# dc-dc.net
KiCad netlist of a schematic drawn in Altium Designer
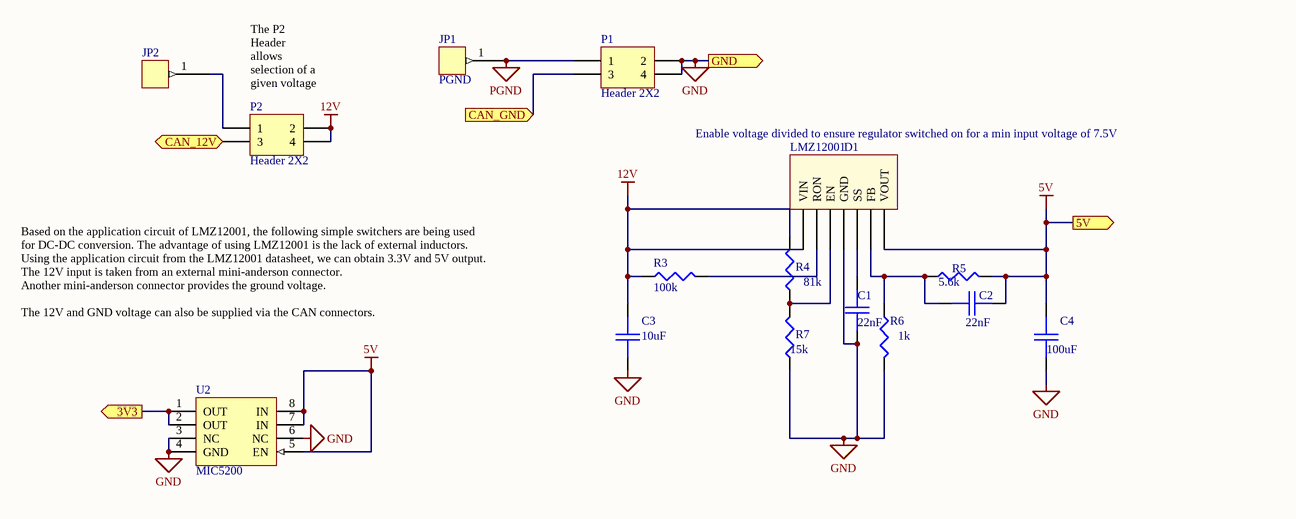
[diagram p0: dc-dc.SchDoc]

(export (version "E")
  (design (tool "Eeschema 10.0.6"))
  (components
    (comp (ref "C1")
      (value "22nF")
      (footprint "0603")
      (description "Capacitor")
      (fields (field (name "Comment") "CAP"))
      (libsource (lib "RCLDQ") (part "CAP"))
    )
    (comp (ref "C2")
      (value "22nF")
      (footprint "0603")
      (description "Capacitor")
      (fields (field (name "Comment") "CAP"))
      (libsource (lib "RCLDQ") (part "CAP"))
    )
    (comp (ref "C3")
      (value "10uF")
      (footprint "1206")
      (description "Capacitor")
      (fields (field (name "Comment") "CAP"))
      (libsource (lib "RCLDQ") (part "CAP"))
    )
    (comp (ref "C4")
      (value "100uF")
      (footprint "1206")
      (description "Capacitor")
      (fields (field (name "Comment") "CAP"))
      (libsource (lib "RCLDQ") (part "CAP"))
    )
    (comp (ref "D1")
      (value "DC-DC SWITCHER")
      (footprint "PFM-7")
      (libsource (lib "add-schematic-library") (part "lmz12001"))
    )
    (comp (ref "JP1")
      (value "PGND")
      (footprint "POWERPOLE25A")
      (description "Power Ground (currently assumed that it is provided through a min-anderson connector)")
      (libsource (lib "Connectors") (part "CON1"))
    )
    (comp (ref "JP2")
      (value "CON1")
      (footprint "POWERPOLE25A")
      (description "Currently assumed that the mini-anderson connector provides 12V")
      (libsource (lib "Connectors") (part "CON1"))
    )
    (comp (ref "P1")
      (value "Header 2X2")
      (footprint "HDR2X2")
      (description "Header, 2-Pin, Dual row")
      (fields (field (name "PUBLISHER") "Altium Limited"))
      (libsource (lib "Miscellaneous Connectors") (part "Header 2X2"))
    )
    (comp (ref "P2")
      (value "Header 2X2")
      (footprint "HDR2X2")
      (description "Header, 2-Pin, Dual row")
      (fields (field (name "PUBLISHER") "Altium Limited"))
      (libsource (lib "Miscellaneous Connectors") (part "Header 2X2"))
    )
    (comp (ref "R3")
      (value "100k")
      (footprint "0603")
      (description "Resistor")
      (fields (field (name "Comment") "RES1"))
      (libsource (lib "RCLDQ") (part "RES1"))
    )
    (comp (ref "R4")
      (value "81k")
      (footprint "0603")
      (description "Resistor")
      (fields (field (name "Comment") "RES1"))
      (libsource (lib "RCLDQ") (part "RES1"))
    )
    (comp (ref "R5")
      (value "5.6k")
      (footprint "0603")
      (description "Resistor")
      (fields (field (name "Comment") "RES1"))
      (libsource (lib "RCLDQ") (part "RES1"))
    )
    (comp (ref "R6")
      (value "1k")
      (footprint "0603")
      (description "Resistor")
      (fields (field (name "Comment") "RES1"))
      (libsource (lib "RCLDQ") (part "RES1"))
    )
    (comp (ref "R7")
      (value "15k")
      (footprint "0603")
      (description "Resistor")
      (fields (field (name "Comment") "RES1"))
      (libsource (lib "RCLDQ") (part "RES1"))
    )
    (comp (ref "U2")
      (value "MIC5200")
      (footprint "SO8")
      (description "MIC5200 - SO8")
      (libsource (lib "Regulators") (part "MIC5200"))
    )
  )
  (nets
    (net (code "1") (name "/3V3") (class "Default")
      (node (ref "U2") (pin "1") (pinfunction "OUT_1") (pintype "power_in"))
      (node (ref "U2") (pin "2") (pinfunction "OUT_2") (pintype "power_in"))
    )
    (net (code "2") (name "/CAN_12V") (class "Default")
      (node (ref "P2") (pin "3") (pinfunction "3_3") (pintype "passive"))
    )
    (net (code "3") (name "/CAN_GND") (class "Default")
      (node (ref "P1") (pin "3") (pinfunction "3_3") (pintype "passive"))
    )
    (net (code "4") (name "5V") (class "Default")
      (node (ref "C2") (pin "2") (pinfunction "2_2") (pintype "passive"))
      (node (ref "C4") (pin "1") (pinfunction "1_1") (pintype "passive"))
      (node (ref "D1") (pin "7") (pinfunction "VOUT_7") (pintype "passive"))
      (node (ref "R5") (pin "2") (pinfunction "2_2") (pintype "passive"))
      (node (ref "U2") (pin "5") (pinfunction "EN_5") (pintype "input"))
      (node (ref "U2") (pin "7") (pinfunction "IN_7") (pintype "power_in"))
      (node (ref "U2") (pin "8") (pinfunction "IN_8") (pintype "power_in"))
    )
    (net (code "5") (name "12V") (class "Default")
      (node (ref "C3") (pin "1") (pinfunction "1_1") (pintype "passive"))
      (node (ref "D1") (pin "1") (pinfunction "VIN_1") (pintype "passive"))
      (node (ref "P2") (pin "2") (pinfunction "2_2") (pintype "passive"))
      (node (ref "P2") (pin "4") (pinfunction "4_4") (pintype "passive"))
      (node (ref "R3") (pin "1") (pinfunction "1_1") (pintype "passive"))
      (node (ref "R4") (pin "2") (pinfunction "2_2") (pintype "passive"))
    )
    (net (code "6") (name "GND") (class "Default")
      (node (ref "C1") (pin "2") (pinfunction "2_2") (pintype "passive"))
      (node (ref "C3") (pin "2") (pinfunction "2_2") (pintype "passive"))
      (node (ref "C4") (pin "2") (pinfunction "2_2") (pintype "passive"))
      (node (ref "D1") (pin "4") (pinfunction "GND_4") (pintype "passive"))
      (node (ref "P1") (pin "2") (pinfunction "2_2") (pintype "passive"))
      (node (ref "P1") (pin "4") (pinfunction "4_4") (pintype "passive"))
      (node (ref "R6") (pin "2") (pinfunction "2_2") (pintype "passive"))
      (node (ref "R7") (pin "1") (pinfunction "1_1") (pintype "passive"))
      (node (ref "U2") (pin "3") (pinfunction "NC_3") (pintype "passive"))
      (node (ref "U2") (pin "4") (pinfunction "GND_4") (pintype "power_in"))
      (node (ref "U2") (pin "6") (pinfunction "NC_6") (pintype "passive"))
    )
    (net (code "7") (name "Net-(D1-EN)") (class "Default")
      (node (ref "D1") (pin "3") (pinfunction "EN_3") (pintype "passive"))
      (node (ref "R4") (pin "1") (pinfunction "1_1") (pintype "passive"))
      (node (ref "R7") (pin "2") (pinfunction "2_2") (pintype "passive"))
    )
    (net (code "8") (name "Net-(D1-FB)") (class "Default")
      (node (ref "C2") (pin "1") (pinfunction "1_1") (pintype "passive"))
      (node (ref "D1") (pin "6") (pinfunction "FB_6") (pintype "passive"))
      (node (ref "R5") (pin "1") (pinfunction "1_1") (pintype "passive"))
      (node (ref "R6") (pin "1") (pinfunction "1_1") (pintype "passive"))
    )
    (net (code "9") (name "Net-(D1-RON)") (class "Default")
      (node (ref "D1") (pin "2") (pinfunction "RON_2") (pintype "passive"))
      (node (ref "R3") (pin "2") (pinfunction "2_2") (pintype "passive"))
    )
    (net (code "10") (name "Net-(D1-SS)") (class "Default")
      (node (ref "C1") (pin "1") (pinfunction "1_1") (pintype "passive"))
      (node (ref "D1") (pin "5") (pinfunction "SS_5") (pintype "passive"))
    )
    (net (code "11") (name "Net-(JP2-Pad1)") (class "Default")
      (node (ref "JP2") (pin "1") (pinfunction "1_1") (pintype "output"))
      (node (ref "P2") (pin "1") (pinfunction "1_1") (pintype "passive"))
    )
    (net (code "12") (name "PGND") (class "Default")
      (node (ref "JP1") (pin "1") (pinfunction "1_1") (pintype "output"))
      (node (ref "P1") (pin "1") (pinfunction "1_1") (pintype "passive"))
    )
  )
)
